# G118_9563_Demo.net
KiCad netlist of a schematic drawn in Altium Designer
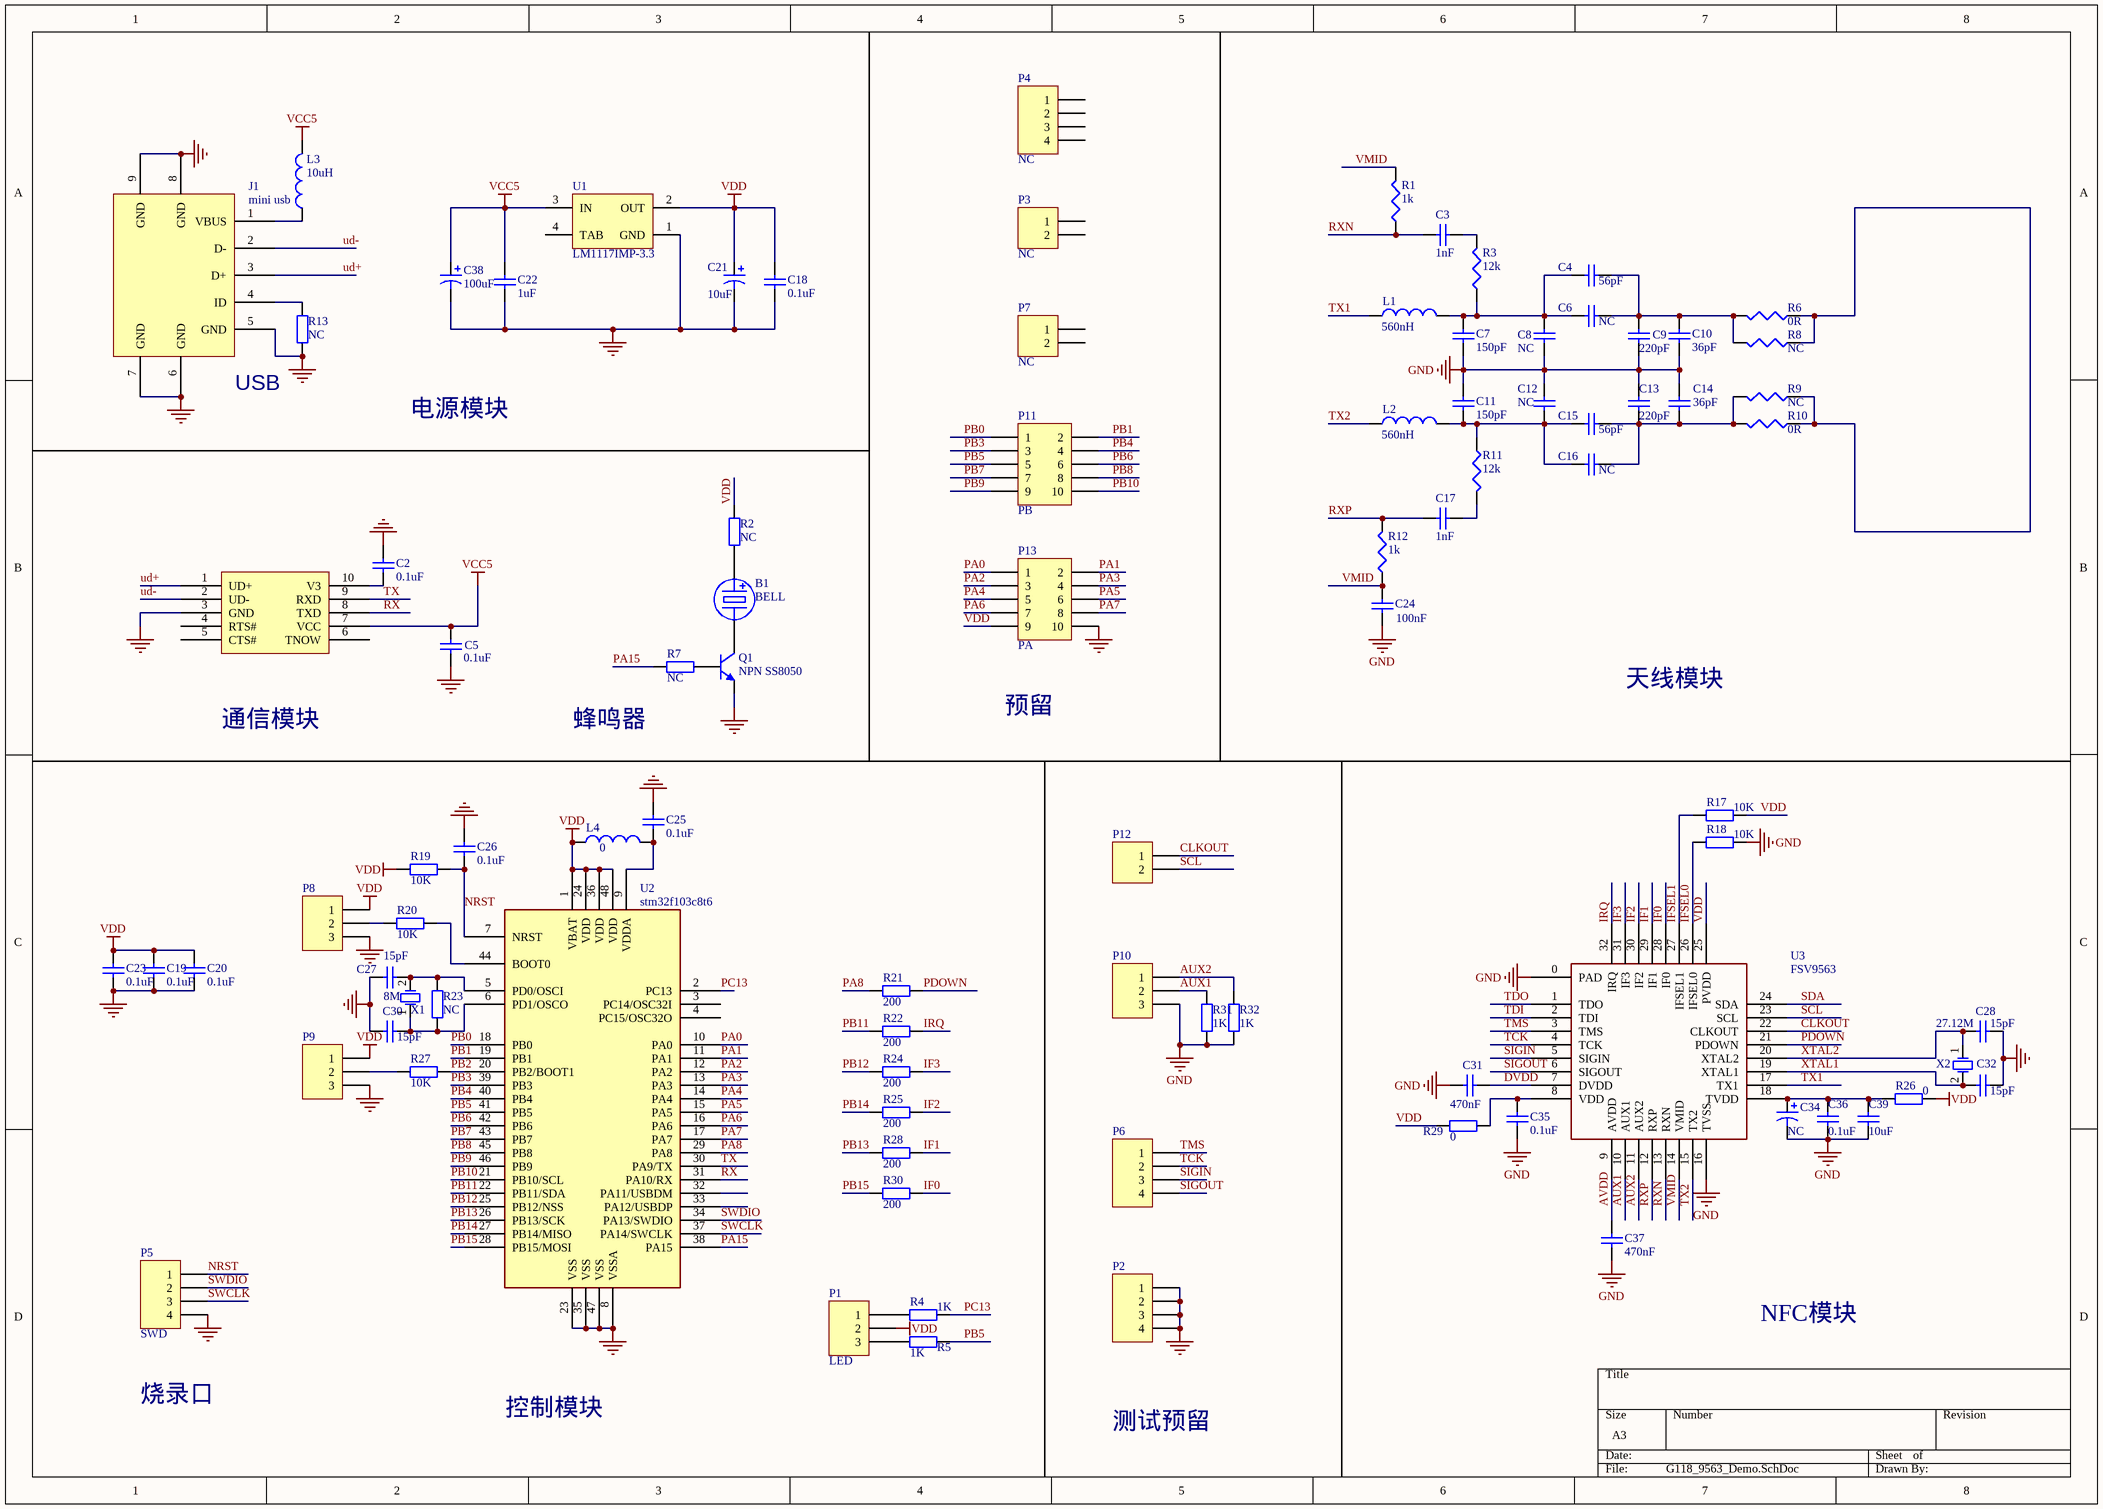
[diagram p0: G118_9563_Demo.SchDoc]

(export (version "E")
  (design (tool "Eeschema 10.0.6"))
  (components
    (comp (ref "B1") (value "BELL") (footprint "BELL_S") (libsource (lib "DevicePlus") (part "BELL")))
    (comp (ref "C2") (value "0.1uF") (footprint "0704C") (libsource (lib "DevicePlus") (part "Capacitor")))
    (comp (ref "C3")
      (value "1nF")
      (footprint "0704C")
      (description "Capacitor (Semiconductor SIM Model)")
      (fields (field (name "Comment") "Cap Semi") (field (name "PUBLISHER") "Altium Limited"))
      (libsource (lib "Miscellaneous Devices") (part "Cap Semi"))
    )
    (comp (ref "C4")
      (value "56pF")
      (footprint "0704C")
      (description "Capacitor (Semiconductor SIM Model)")
      (fields (field (name "Comment") "Cap Semi") (field (name "PUBLISHER") "Altium Limited"))
      (libsource (lib "Miscellaneous Devices") (part "Cap Semi"))
    )
    (comp (ref "C5") (value "0.1uF") (footprint "0704C") (libsource (lib "DevicePlus") (part "Capacitor")))
    (comp (ref "C6")
      (value "NC")
      (footprint "0704C")
      (description "Capacitor (Semiconductor SIM Model)")
      (fields (field (name "Comment") "Cap Semi") (field (name "PUBLISHER") "Altium Limited"))
      (libsource (lib "Miscellaneous Devices") (part "Cap Semi"))
    )
    (comp (ref "C7")
      (value "150pF")
      (footprint "0704C")
      (description "Capacitor (Semiconductor SIM Model)")
      (fields (field (name "Comment") "Cap Semi") (field (name "PUBLISHER") "Altium Limited"))
      (libsource (lib "Miscellaneous Devices") (part "Cap Semi"))
    )
    (comp (ref "C8")
      (value "NC")
      (footprint "0704C")
      (description "Capacitor (Semiconductor SIM Model)")
      (fields (field (name "Comment") "Cap Semi") (field (name "PUBLISHER") "Altium Limited"))
      (libsource (lib "Miscellaneous Devices") (part "Cap Semi"))
    )
    (comp (ref "C9")
      (value "220pF")
      (footprint "0704C")
      (description "Capacitor (Semiconductor SIM Model)")
      (fields (field (name "Comment") "Cap Semi") (field (name "PUBLISHER") "Altium Limited"))
      (libsource (lib "Miscellaneous Devices") (part "Cap Semi"))
    )
    (comp (ref "C10")
      (value "36pF")
      (footprint "0704C")
      (description "Capacitor (Semiconductor SIM Model)")
      (fields (field (name "Comment") "Cap Semi") (field (name "PUBLISHER") "Altium Limited"))
      (libsource (lib "Miscellaneous Devices") (part "Cap Semi"))
    )
    (comp (ref "C11")
      (value "150pF")
      (footprint "0704C")
      (description "Capacitor (Semiconductor SIM Model)")
      (fields (field (name "Comment") "Cap Semi") (field (name "PUBLISHER") "Altium Limited"))
      (libsource (lib "Miscellaneous Devices") (part "Cap Semi"))
    )
    (comp (ref "C12")
      (value "NC")
      (footprint "0704C")
      (description "Capacitor (Semiconductor SIM Model)")
      (fields (field (name "Comment") "Cap Semi") (field (name "PUBLISHER") "Altium Limited"))
      (libsource (lib "Miscellaneous Devices") (part "Cap Semi"))
    )
    (comp (ref "C13")
      (value "220pF")
      (footprint "0704C")
      (description "Capacitor (Semiconductor SIM Model)")
      (fields (field (name "Comment") "Cap Semi") (field (name "PUBLISHER") "Altium Limited"))
      (libsource (lib "Miscellaneous Devices") (part "Cap Semi"))
    )
    (comp (ref "C14")
      (value "36pF")
      (footprint "0704C")
      (description "Capacitor (Semiconductor SIM Model)")
      (fields (field (name "Comment") "Cap Semi") (field (name "PUBLISHER") "Altium Limited"))
      (libsource (lib "Miscellaneous Devices") (part "Cap Semi"))
    )
    (comp (ref "C15")
      (value "56pF")
      (footprint "0704C")
      (description "Capacitor (Semiconductor SIM Model)")
      (fields (field (name "Comment") "Cap Semi") (field (name "PUBLISHER") "Altium Limited"))
      (libsource (lib "Miscellaneous Devices") (part "Cap Semi"))
    )
    (comp (ref "C16")
      (value "NC")
      (footprint "0704C")
      (description "Capacitor (Semiconductor SIM Model)")
      (fields (field (name "Comment") "Cap Semi") (field (name "PUBLISHER") "Altium Limited"))
      (libsource (lib "Miscellaneous Devices") (part "Cap Semi"))
    )
    (comp (ref "C17")
      (value "1nF")
      (footprint "0704C")
      (description "Capacitor (Semiconductor SIM Model)")
      (fields (field (name "Comment") "Cap Semi") (field (name "PUBLISHER") "Altium Limited"))
      (libsource (lib "Miscellaneous Devices") (part "Cap Semi"))
    )
    (comp (ref "C18") (value "0.1uF") (footprint "0704C") (libsource (lib "DevicePlus") (part "Capacitor")))
    (comp (ref "C19") (value "0.1uF") (footprint "0704C") (libsource (lib "DevicePlus") (part "Capacitor")))
    (comp (ref "C20") (value "0.1uF") (footprint "0704C") (libsource (lib "DevicePlus") (part "Capacitor")))
    (comp (ref "C21") (value "10uF") (footprint "RB.1/.2") (libsource (lib "DevicePlus") (part "CapPolar")))
    (comp (ref "C22") (value "1uF") (footprint "0704C") (libsource (lib "DevicePlus") (part "Capacitor")))
    (comp (ref "C23") (value "0.1uF") (footprint "0704C") (libsource (lib "DevicePlus") (part "Capacitor")))
    (comp (ref "C24")
      (value "100nF")
      (footprint "0704C")
      (description "Capacitor (Semiconductor SIM Model)")
      (fields (field (name "PUBLISHER") "Altium Limited"))
      (libsource (lib "Miscellaneous Devices") (part "Cap Semi"))
    )
    (comp (ref "C25") (value "0.1uF") (footprint "0704C") (libsource (lib "DevicePlus") (part "Capacitor")))
    (comp (ref "C26") (value "0.1uF") (footprint "0704C") (libsource (lib "DevicePlus") (part "Capacitor")))
    (comp (ref "C27") (value "15pF") (footprint "0704C") (libsource (lib "DevicePlus") (part "Capacitor")))
    (comp (ref "C28") (value "15pF") (footprint "0704C") (libsource (lib "DevicePlus") (part "Capacitor")))
    (comp (ref "C30") (value "15pF") (footprint "0704C") (libsource (lib "DevicePlus") (part "Capacitor")))
    (comp (ref "C31")
      (value "470nF")
      (footprint "0704C")
      (description "Capacitor (Semiconductor SIM Model)")
      (fields (field (name "Comment") "Cap Semi") (field (name "PUBLISHER") "Altium Limited"))
      (libsource (lib "Miscellaneous Devices") (part "Cap Semi"))
    )
    (comp (ref "C32") (value "15pF") (footprint "0704C") (libsource (lib "DevicePlus") (part "Capacitor")))
    (comp (ref "C34") (value "NC") (footprint "RB.1/.2") (libsource (lib "DevicePlus") (part "CapPolar")))
    (comp (ref "C35") (value "0.1uF") (footprint "0704C") (libsource (lib "DevicePlus") (part "Capacitor")))
    (comp (ref "C36") (value "0.1uF") (footprint "0704C") (libsource (lib "DevicePlus") (part "Capacitor")))
    (comp (ref "C37")
      (value "470nF")
      (footprint "0704C")
      (description "Capacitor (Semiconductor SIM Model)")
      (fields (field (name "Comment") "Cap Semi") (field (name "PUBLISHER") "Altium Limited"))
      (libsource (lib "Miscellaneous Devices") (part "Cap Semi"))
    )
    (comp (ref "C38") (value "100uF") (footprint "RB.1/.2") (libsource (lib "DevicePlus") (part "CapPolar")))
    (comp (ref "C39") (value "10uF") (footprint "0704C") (libsource (lib "DevicePlus") (part "Capacitor")))
    (comp (ref "CH1") (value "CH340E") (footprint "msop-10") (libsource (lib "ch340e") (part "CH340E")))
    (comp (ref "J1")
      (value "mini usb")
      (footprint "usb_mini")
      (libsource (lib "SOCKET_Sch") (part "MINI_USB"))
    )
    (comp (ref "L1")
      (value "560nH")
      (footprint "1210L")
      (description "Inductor")
      (fields (field (name "PUBLISHER") "Altium Limited"))
      (libsource (lib "Miscellaneous Devices") (part "Inductor"))
    )
    (comp (ref "L2")
      (value "560nH")
      (footprint "1210L")
      (description "Inductor")
      (fields (field (name "PUBLISHER") "Altium Limited"))
      (libsource (lib "Miscellaneous Devices") (part "Inductor"))
    )
    (comp (ref "L3") (value "10uH") (footprint "1206") (libsource (lib "DevicePlus") (part "Inductor")))
    (comp (ref "L4") (value "0") (footprint "1206") (libsource (lib "DevicePlus") (part "Inductor")))
    (comp (ref "P1")
      (value "LED")
      (footprint "HDR1X3")
      (description "Header, 3-Pin")
      (fields (field (name "PUBLISHER") "Altium Limited"))
      (libsource (lib "Miscellaneous Connectors") (part "Header 3"))
    )
    (comp (ref "P2")
      (value "~")
      (footprint "HDR1X4")
      (description "Header, 4-Pin")
      (fields (field (name "PUBLISHER") "Altium Limited"))
      (libsource (lib "Miscellaneous Connectors") (part "Header 4"))
    )
    (comp (ref "P3")
      (value "NC")
      (footprint "HDR1X2")
      (description "Header, 2-Pin")
      (fields (field (name "PUBLISHER") "Altium Limited"))
      (libsource (lib "Miscellaneous Connectors") (part "Header 2"))
    )
    (comp (ref "P4")
      (value "NC")
      (footprint "HDR1X4")
      (description "Header, 4-Pin")
      (fields (field (name "PUBLISHER") "Altium Limited"))
      (libsource (lib "Miscellaneous Connectors") (part "Header 4"))
    )
    (comp (ref "P5")
      (value "SWD")
      (footprint "HDR1X4")
      (description "Header, 4-Pin")
      (fields (field (name "PUBLISHER") "Altium Limited"))
      (libsource (lib "Miscellaneous Connectors") (part "Header 4"))
    )
    (comp (ref "P6")
      (value "~")
      (footprint "HDR1X4")
      (description "Header, 4-Pin")
      (fields (field (name "PUBLISHER") "Altium Limited"))
      (libsource (lib "Miscellaneous Connectors") (part "Header 4"))
    )
    (comp (ref "P7")
      (value "NC")
      (footprint "HDR1X2")
      (description "Header, 2-Pin")
      (fields (field (name "PUBLISHER") "Altium Limited"))
      (libsource (lib "Miscellaneous Connectors") (part "Header 2"))
    )
    (comp (ref "P8")
      (value "~")
      (footprint "HDR1X3")
      (description "Header, 3-Pin")
      (fields (field (name "PUBLISHER") "Altium Limited"))
      (libsource (lib "Miscellaneous Connectors") (part "Header 3"))
    )
    (comp (ref "P9")
      (value "~")
      (footprint "HDR1X3")
      (description "Header, 3-Pin")
      (fields (field (name "PUBLISHER") "Altium Limited"))
      (libsource (lib "Miscellaneous Connectors") (part "Header 3"))
    )
    (comp (ref "P10")
      (value "~")
      (footprint "HDR1X3")
      (description "Header, 3-Pin")
      (fields (field (name "PUBLISHER") "Altium Limited"))
      (libsource (lib "Miscellaneous Connectors") (part "Header 3"))
    )
    (comp (ref "P11")
      (value "PB")
      (footprint "HDR2X5")
      (description "Header, 5-Pin, Dual row")
      (fields (field (name "PUBLISHER") "Altium Limited"))
      (libsource (lib "Miscellaneous Connectors") (part "Header 5X2"))
    )
    (comp (ref "P12")
      (value "~")
      (footprint "HDR1X2")
      (description "Header, 2-Pin")
      (fields (field (name "PUBLISHER") "Altium Limited"))
      (libsource (lib "Miscellaneous Connectors") (part "Header 2"))
    )
    (comp (ref "P13")
      (value "PA")
      (footprint "HDR2X5")
      (description "Header, 5-Pin, Dual row")
      (fields (field (name "PUBLISHER") "Altium Limited"))
      (libsource (lib "Miscellaneous Connectors") (part "Header 5X2"))
    )
    (comp (ref "Q1") (value "NPN SS8050") (footprint "SOT-23-2") (libsource (lib "MLIB") (part "NPN SS8050")))
    (comp (ref "R1")
      (value "1k")
      (footprint "0704")
      (description "Resistor")
      (fields (field (name "Comment") "Res3") (field (name "PUBLISHER") "Altium Limited"))
      (libsource (lib "Miscellaneous Devices") (part "Res3"))
    )
    (comp (ref "R2") (value "NC") (footprint "0704") (libsource (lib "") (part "RES_1")))
    (comp (ref "R3")
      (value "12k")
      (footprint "0704")
      (description "Resistor")
      (fields (field (name "Comment") "Res3") (field (name "PUBLISHER") "Altium Limited"))
      (libsource (lib "Miscellaneous Devices") (part "Res3"))
    )
    (comp (ref "R4") (value "1K") (footprint "0704") (libsource (lib "DevicePlus") (part "RES")))
    (comp (ref "R5") (value "1K") (footprint "0704") (libsource (lib "") (part "RES_3")))
    (comp (ref "R6")
      (value "0R")
      (footprint "0704")
      (description "Resistor")
      (fields (field (name "Comment") "Res3") (field (name "PUBLISHER") "Altium Limited"))
      (libsource (lib "Miscellaneous Devices") (part "Res3"))
    )
    (comp (ref "R7") (value "NC") (footprint "0704") (libsource (lib "DevicePlus") (part "RES")))
    (comp (ref "R8")
      (value "NC")
      (footprint "0704")
      (description "Resistor")
      (fields (field (name "Comment") "Res3") (field (name "PUBLISHER") "Altium Limited"))
      (libsource (lib "Miscellaneous Devices") (part "Res3"))
    )
    (comp (ref "R9")
      (value "NC")
      (footprint "0704")
      (description "Resistor")
      (fields (field (name "Comment") "Res3") (field (name "PUBLISHER") "Altium Limited"))
      (libsource (lib "Miscellaneous Devices") (part "Res3"))
    )
    (comp (ref "R10")
      (value "0R")
      (footprint "0704")
      (description "Resistor")
      (fields (field (name "Comment") "Res3") (field (name "PUBLISHER") "Altium Limited"))
      (libsource (lib "Miscellaneous Devices") (part "Res3"))
    )
    (comp (ref "R11")
      (value "12k")
      (footprint "0704")
      (description "Resistor")
      (fields (field (name "Comment") "Res3") (field (name "PUBLISHER") "Altium Limited"))
      (libsource (lib "Miscellaneous Devices") (part "Res3"))
    )
    (comp (ref "R12")
      (value "1k")
      (footprint "0704")
      (description "Resistor")
      (fields (field (name "Comment") "Res3") (field (name "PUBLISHER") "Altium Limited"))
      (libsource (lib "Miscellaneous Devices") (part "Res3"))
    )
    (comp (ref "R13") (value "NC") (footprint "0704") (libsource (lib "") (part "RES_1")))
    (comp (ref "R17") (value "10K") (footprint "0704") (libsource (lib "DevicePlus") (part "RES")))
    (comp (ref "R18") (value "10K") (footprint "0704") (libsource (lib "DevicePlus") (part "RES")))
    (comp (ref "R19") (value "10K") (footprint "0704") (libsource (lib "DevicePlus") (part "RES")))
    (comp (ref "R20") (value "10K") (footprint "0704") (libsource (lib "DevicePlus") (part "RES")))
    (comp (ref "R21") (value "200") (footprint "0704") (libsource (lib "DevicePlus") (part "RES")))
    (comp (ref "R22") (value "200") (footprint "0704") (libsource (lib "DevicePlus") (part "RES")))
    (comp (ref "R23") (value "NC") (footprint "0704") (libsource (lib "") (part "RES_2")))
    (comp (ref "R24") (value "200") (footprint "0704") (libsource (lib "DevicePlus") (part "RES")))
    (comp (ref "R25") (value "200") (footprint "0704") (libsource (lib "DevicePlus") (part "RES")))
    (comp (ref "R26") (value "0") (footprint "0704") (libsource (lib "DevicePlus") (part "RES")))
    (comp (ref "R27") (value "10K") (footprint "0704") (libsource (lib "DevicePlus") (part "RES")))
    (comp (ref "R28") (value "200") (footprint "0704") (libsource (lib "DevicePlus") (part "RES")))
    (comp (ref "R29") (value "0") (footprint "0704") (libsource (lib "DevicePlus") (part "RES")))
    (comp (ref "R30") (value "200") (footprint "0704") (libsource (lib "DevicePlus") (part "RES")))
    (comp (ref "R31") (value "1K") (footprint "0704") (libsource (lib "") (part "RES_2")))
    (comp (ref "R32") (value "1K") (footprint "0704") (libsource (lib "") (part "RES_2")))
    (comp (ref "U1")
      (value "LM1117IMP-3.3")
      (footprint "MP04A_N")
      (description "800mA Low-Dropout Linear Regulator")
      (fields
        (field (name "MANUFACTURER") "National Semiconductor")
        (field (name "DIGIKEYPARTNUMBER") "LM1117IMP-3.3CT-ND")
        (field (name "PUBLISHER") "Altium Limited")
      )
      (libsource (lib "NSC LDO") (part "LM1117IMP-3.3"))
    )
    (comp (ref "U2")
      (value "stm32f103c8t6")
      (footprint "LQFP48L")
      (libsource (lib "IC_Sch") (part "stm32f103c8t6"))
    )
    (comp (ref "U3")
      (value "FSV9563")
      (footprint "QFN-32")
      (description "NFC DRIVER")
      (libsource (lib "IC_Sch") (part "CLRC663"))
    )
    (comp (ref "X1") (value "8M") (footprint "CRYSTAL") (libsource (lib "DevicePlus") (part "Crystal")))
    (comp (ref "X2") (value "27.12M") (footprint "CRYSTAL") (libsource (lib "DevicePlus") (part "Crystal")))
  )
  (nets
    (net (code "1") (name "/AUX1") (class "Default")
      (node (ref "P10") (pin "2") (pinfunction "2_2") (pintype "passive"))
      (node (ref "R31") (pin "2") (pinfunction "2_2") (pintype "passive"))
      (node (ref "U3") (pin "10") (pinfunction "AUX1_10") (pintype "passive"))
    )
    (net (code "2") (name "/AUX2") (class "Default")
      (node (ref "P10") (pin "1") (pinfunction "1_1") (pintype "passive"))
      (node (ref "R32") (pin "2") (pinfunction "2_2") (pintype "passive"))
      (node (ref "U3") (pin "11") (pinfunction "AUX2_11") (pintype "passive"))
    )
    (net (code "3") (name "/AVDD") (class "Default")
      (node (ref "C37") (pin "2") (pinfunction "2_2") (pintype "passive"))
      (node (ref "U3") (pin "9") (pinfunction "AVDD_9") (pintype "passive"))
    )
    (net (code "4") (name "/CLKOUT") (class "Default")
      (node (ref "P12") (pin "1") (pinfunction "1_1") (pintype "passive"))
      (node (ref "U3") (pin "22") (pinfunction "CLKOUT_22") (pintype "passive"))
    )
    (net (code "5") (name "/DVDD") (class "Default")
      (node (ref "C31") (pin "2") (pinfunction "2_2") (pintype "passive"))
      (node (ref "U3") (pin "7") (pinfunction "DVDD_7") (pintype "passive"))
    )
    (net (code "6") (name "/IF0") (class "Default")
      (node (ref "R30") (pin "2") (pinfunction "2_2") (pintype "passive"))
      (node (ref "U3") (pin "28") (pinfunction "IF0_28") (pintype "passive"))
    )
    (net (code "7") (name "/IF1") (class "Default")
      (node (ref "R28") (pin "2") (pinfunction "2_2") (pintype "passive"))
      (node (ref "U3") (pin "29") (pinfunction "IF1_29") (pintype "passive"))
    )
    (net (code "8") (name "/IF2") (class "Default")
      (node (ref "R25") (pin "2") (pinfunction "2_2") (pintype "passive"))
      (node (ref "U3") (pin "30") (pinfunction "IF2_30") (pintype "passive"))
    )
    (net (code "9") (name "/IF3") (class "Default")
      (node (ref "R24") (pin "2") (pinfunction "2_2") (pintype "passive"))
      (node (ref "U3") (pin "31") (pinfunction "IF3_31") (pintype "passive"))
    )
    (net (code "10") (name "/IFSEL0") (class "Default")
      (node (ref "R18") (pin "1") (pinfunction "1_1") (pintype "passive"))
      (node (ref "U3") (pin "26") (pinfunction "IFSEL0_26") (pintype "passive"))
    )
    (net (code "11") (name "/IFSEL1") (class "Default")
      (node (ref "R17") (pin "1") (pinfunction "1_1") (pintype "passive"))
      (node (ref "U3") (pin "27") (pinfunction "IFSEL1_27") (pintype "passive"))
    )
    (net (code "12") (name "/IRQ") (class "Default")
      (node (ref "R22") (pin "2") (pinfunction "2_2") (pintype "passive"))
      (node (ref "U3") (pin "32") (pinfunction "IRQ_32") (pintype "passive"))
    )
    (net (code "13") (name "/NRST") (class "Default")
      (node (ref "C26") (pin "2") (pinfunction "2_2") (pintype "passive"))
      (node (ref "P5") (pin "1") (pinfunction "1_1") (pintype "passive"))
      (node (ref "R19") (pin "2") (pinfunction "2_2") (pintype "passive"))
      (node (ref "U2") (pin "7") (pinfunction "NRST_7") (pintype "passive"))
    )
    (net (code "14") (name "/PA0") (class "Default")
      (node (ref "P13") (pin "1") (pinfunction "1_1") (pintype "passive"))
      (node (ref "U2") (pin "10") (pinfunction "PA0_10") (pintype "passive"))
    )
    (net (code "15") (name "/PA1") (class "Default")
      (node (ref "P13") (pin "2") (pinfunction "2_2") (pintype "passive"))
      (node (ref "U2") (pin "11") (pinfunction "PA1_11") (pintype "passive"))
    )
    (net (code "16") (name "/PA2") (class "Default")
      (node (ref "P13") (pin "3") (pinfunction "3_3") (pintype "passive"))
      (node (ref "U2") (pin "12") (pinfunction "PA2_12") (pintype "passive"))
    )
    (net (code "17") (name "/PA3") (class "Default")
      (node (ref "P13") (pin "4") (pinfunction "4_4") (pintype "passive"))
      (node (ref "U2") (pin "13") (pinfunction "PA3_13") (pintype "passive"))
    )
    (net (code "18") (name "/PA4") (class "Default")
      (node (ref "P13") (pin "5") (pinfunction "5_5") (pintype "passive"))
      (node (ref "U2") (pin "14") (pinfunction "PA4_14") (pintype "passive"))
    )
    (net (code "19") (name "/PA5") (class "Default")
      (node (ref "P13") (pin "6") (pinfunction "6_6") (pintype "passive"))
      (node (ref "U2") (pin "15") (pinfunction "PA5_15") (pintype "passive"))
    )
    (net (code "20") (name "/PA6") (class "Default")
      (node (ref "P13") (pin "7") (pinfunction "7_7") (pintype "passive"))
      (node (ref "U2") (pin "16") (pinfunction "PA6_16") (pintype "passive"))
    )
    (net (code "21") (name "/PA7") (class "Default")
      (node (ref "P13") (pin "8") (pinfunction "8_8") (pintype "passive"))
      (node (ref "U2") (pin "17") (pinfunction "PA7_17") (pintype "passive"))
    )
    (net (code "22") (name "/PA8") (class "Default")
      (node (ref "R21") (pin "1") (pinfunction "1_1") (pintype "passive"))
      (node (ref "U2") (pin "29") (pinfunction "PA8_29") (pintype "passive"))
    )
    (net (code "23") (name "/PA15") (class "Default")
      (node (ref "R7") (pin "1") (pinfunction "1_1") (pintype "passive"))
      (node (ref "U2") (pin "38") (pinfunction "PA15_38") (pintype "passive"))
    )
    (net (code "24") (name "/PB0") (class "Default")
      (node (ref "P11") (pin "1") (pinfunction "1_1") (pintype "passive"))
      (node (ref "U2") (pin "18") (pinfunction "PB0_18") (pintype "passive"))
    )
    (net (code "25") (name "/PB1") (class "Default")
      (node (ref "P11") (pin "2") (pinfunction "2_2") (pintype "passive"))
      (node (ref "U2") (pin "19") (pinfunction "PB1_19") (pintype "passive"))
    )
    (net (code "26") (name "/PB2") (class "Default")
      (node (ref "R27") (pin "2") (pinfunction "2_2") (pintype "passive"))
      (node (ref "U2") (pin "20") (pinfunction "PB2/BOOT1_20") (pintype "passive"))
    )
    (net (code "27") (name "/PB3") (class "Default")
      (node (ref "P11") (pin "3") (pinfunction "3_3") (pintype "passive"))
      (node (ref "U2") (pin "39") (pinfunction "PB3_39") (pintype "passive"))
    )
    (net (code "28") (name "/PB4") (class "Default")
      (node (ref "P11") (pin "4") (pinfunction "4_4") (pintype "passive"))
      (node (ref "U2") (pin "40") (pinfunction "PB4_40") (pintype "passive"))
    )
    (net (code "29") (name "/PB5") (class "Default")
      (node (ref "P11") (pin "5") (pinfunction "5_5") (pintype "passive"))
      (node (ref "R5") (pin "1") (pinfunction "1_1") (pintype "passive"))
      (node (ref "U2") (pin "41") (pinfunction "PB5_41") (pintype "passive"))
    )
    (net (code "30") (name "/PB6") (class "Default")
      (node (ref "P11") (pin "6") (pinfunction "6_6") (pintype "passive"))
      (node (ref "U2") (pin "42") (pinfunction "PB6_42") (pintype "passive"))
    )
    (net (code "31") (name "/PB7") (class "Default")
      (node (ref "P11") (pin "7") (pinfunction "7_7") (pintype "passive"))
      (node (ref "U2") (pin "43") (pinfunction "PB7_43") (pintype "passive"))
    )
    (net (code "32") (name "/PB8") (class "Default")
      (node (ref "P11") (pin "8") (pinfunction "8_8") (pintype "passive"))
      (node (ref "U2") (pin "45") (pinfunction "PB8_45") (pintype "passive"))
    )
    (net (code "33") (name "/PB9") (class "Default")
      (node (ref "P11") (pin "9") (pinfunction "9_9") (pintype "passive"))
      (node (ref "U2") (pin "46") (pinfunction "PB9_46") (pintype "passive"))
    )
    (net (code "34") (name "/PB10") (class "Default")
      (node (ref "P11") (pin "10") (pinfunction "10_10") (pintype "passive"))
      (node (ref "U2") (pin "21") (pinfunction "PB10/SCL_21") (pintype "passive"))
    )
    (net (code "35") (name "/PB11") (class "Default")
      (node (ref "R22") (pin "1") (pinfunction "1_1") (pintype "passive"))
      (node (ref "U2") (pin "22") (pinfunction "PB11/SDA_22") (pintype "passive"))
    )
    (net (code "36") (name "/PB12") (class "Default")
      (node (ref "R24") (pin "1") (pinfunction "1_1") (pintype "passive"))
      (node (ref "U2") (pin "25") (pinfunction "PB12/NSS_25") (pintype "passive"))
    )
    (net (code "37") (name "/PB13") (class "Default")
      (node (ref "R28") (pin "1") (pinfunction "1_1") (pintype "passive"))
      (node (ref "U2") (pin "26") (pinfunction "PB13/SCK_26") (pintype "passive"))
    )
    (net (code "38") (name "/PB14") (class "Default")
      (node (ref "R25") (pin "1") (pinfunction "1_1") (pintype "passive"))
      (node (ref "U2") (pin "27") (pinfunction "PB14/MISO_27") (pintype "passive"))
    )
    (net (code "39") (name "/PB15") (class "Default")
      (node (ref "R30") (pin "1") (pinfunction "1_1") (pintype "passive"))
      (node (ref "U2") (pin "28") (pinfunction "PB15/MOSI_28") (pintype "passive"))
    )
    (net (code "40") (name "/PC13") (class "Default")
      (node (ref "R4") (pin "2") (pinfunction "2_2") (pintype "passive"))
      (node (ref "U2") (pin "2") (pinfunction "PC13_2") (pintype "passive"))
    )
    (net (code "41") (name "/PDOWN") (class "Default")
      (node (ref "R21") (pin "2") (pinfunction "2_2") (pintype "passive"))
      (node (ref "U3") (pin "21") (pinfunction "PDOWN_21") (pintype "passive"))
    )
    (net (code "42") (name "/RX") (class "Default")
      (node (ref "CH1") (pin "8") (pinfunction "TXD_8") (pintype "passive"))
      (node (ref "U2") (pin "31") (pinfunction "PA10/RX_31") (pintype "passive"))
    )
    (net (code "43") (name "/RXN") (class "Default")
      (node (ref "C3") (pin "2") (pinfunction "2_2") (pintype "passive"))
      (node (ref "R1") (pin "1") (pinfunction "1_1") (pintype "passive"))
      (node (ref "U3") (pin "13") (pinfunction "RXN_13") (pintype "passive"))
    )
    (net (code "44") (name "/RXP") (class "Default")
      (node (ref "C17") (pin "2") (pinfunction "2_2") (pintype "passive"))
      (node (ref "R12") (pin "1") (pinfunction "1_1") (pintype "passive"))
      (node (ref "U3") (pin "12") (pinfunction "RXP_12") (pintype "passive"))
    )
    (net (code "45") (name "/SCL") (class "Default")
      (node (ref "P12") (pin "2") (pinfunction "2_2") (pintype "passive"))
      (node (ref "U3") (pin "23") (pinfunction "SCL_23") (pintype "passive"))
    )
    (net (code "46") (name "/SDA") (class "Default")
      (node (ref "U3") (pin "24") (pinfunction "SDA_24") (pintype "passive"))
    )
    (net (code "47") (name "/SIGIN") (class "Default")
      (node (ref "P6") (pin "3") (pinfunction "3_3") (pintype "passive"))
      (node (ref "U3") (pin "5") (pinfunction "SIGIN_5") (pintype "passive"))
    )
    (net (code "48") (name "/SIGOUT") (class "Default")
      (node (ref "P6") (pin "4") (pinfunction "4_4") (pintype "passive"))
      (node (ref "U3") (pin "6") (pinfunction "SIGOUT_6") (pintype "passive"))
    )
    (net (code "49") (name "/SWCLK") (class "Default")
      (node (ref "P5") (pin "3") (pinfunction "3_3") (pintype "passive"))
      (node (ref "U2") (pin "37") (pinfunction "PA14/SWCLK_37") (pintype "passive"))
    )
    (net (code "50") (name "/SWDIO") (class "Default")
      (node (ref "P5") (pin "2") (pinfunction "2_2") (pintype "passive"))
      (node (ref "U2") (pin "34") (pinfunction "PA13/SWDIO_34") (pintype "passive"))
    )
    (net (code "51") (name "/TCK") (class "Default")
      (node (ref "P6") (pin "2") (pinfunction "2_2") (pintype "passive"))
      (node (ref "U3") (pin "4") (pinfunction "TCK_4") (pintype "passive"))
    )
    (net (code "52") (name "/TDI") (class "Default")
      (node (ref "U3") (pin "2") (pinfunction "TDI_2") (pintype "passive"))
    )
    (net (code "53") (name "/TDO") (class "Default")
      (node (ref "U3") (pin "1") (pinfunction "TDO_1") (pintype "passive"))
    )
    (net (code "54") (name "/TMS") (class "Default")
      (node (ref "P6") (pin "1") (pinfunction "1_1") (pintype "passive"))
      (node (ref "U3") (pin "3") (pinfunction "TMS_3") (pintype "passive"))
    )
    (net (code "55") (name "/TX") (class "Default")
      (node (ref "CH1") (pin "9") (pinfunction "RXD_9") (pintype "passive"))
      (node (ref "U2") (pin "30") (pinfunction "PA9/TX_30") (pintype "passive"))
    )
    (net (code "56") (name "/TX1") (class "Default")
      (node (ref "L1") (pin "1") (pinfunction "1_1") (pintype "passive"))
      (node (ref "U3") (pin "17") (pinfunction "TX1_17") (pintype "passive"))
    )
    (net (code "57") (name "/TX2") (class "Default")
      (node (ref "L2") (pin "1") (pinfunction "1_1") (pintype "passive"))
      (node (ref "U3") (pin "15") (pinfunction "TX2_15") (pintype "passive"))
    )
    (net (code "58") (name "/VMID") (class "Default")
      (node (ref "C24") (pin "1") (pinfunction "1_1") (pintype "passive"))
      (node (ref "R1") (pin "2") (pinfunction "2_2") (pintype "passive"))
      (node (ref "R12") (pin "2") (pinfunction "2_2") (pintype "passive"))
      (node (ref "U3") (pin "14") (pinfunction "VMID_14") (pintype "passive"))
    )
    (net (code "59") (name "/XTAL1") (class "Default")
      (node (ref "C32") (pin "2") (pinfunction "2_2") (pintype "passive"))
      (node (ref "U3") (pin "19") (pinfunction "XTAL1_19") (pintype "passive"))
      (node (ref "X2") (pin "2") (pinfunction "OSC2_2") (pintype "passive"))
    )
    (net (code "60") (name "/XTAL2") (class "Default")
      (node (ref "C28") (pin "2") (pinfunction "2_2") (pintype "passive"))
      (node (ref "U3") (pin "20") (pinfunction "XTAL2_20") (pintype "passive"))
      (node (ref "X2") (pin "1") (pinfunction "OSC1_1") (pintype "passive"))
    )
    (net (code "61") (name "/ud+") (class "Default")
      (node (ref "CH1") (pin "1") (pinfunction "UD+_1") (pintype "power_in"))
      (node (ref "J1") (pin "3") (pinfunction "D+_3") (pintype "passive"))
    )
    (net (code "62") (name "/ud-") (class "Default")
      (node (ref "CH1") (pin "2") (pinfunction "UD-_2") (pintype "passive"))
      (node (ref "J1") (pin "2") (pinfunction "D-_2") (pintype "passive"))
    )
    (net (code "63") (name "GND") (class "Default")
      (node (ref "C10") (pin "2") (pinfunction "2_2") (pintype "passive"))
      (node (ref "C11") (pin "1") (pinfunction "1_1") (pintype "passive"))
      (node (ref "C12") (pin "1") (pinfunction "1_1") (pintype "passive"))
      (node (ref "C13") (pin "1") (pinfunction "1_1") (pintype "passive"))
      (node (ref "C14") (pin "1") (pinfunction "1_1") (pintype "passive"))
      (node (ref "C18") (pin "2") (pinfunction "2_2") (pintype "passive"))
      (node (ref "C19") (pin "2") (pinfunction "2_2") (pintype "passive"))
      (node (ref "C2") (pin "2") (pinfunction "2_2") (pintype "passive"))
      (node (ref "C20") (pin "2") (pinfunction "2_2") (pintype "passive"))
      (node (ref "C21") (pin "2") (pinfunction "2_2") (pintype "passive"))
      (node (ref "C22") (pin "2") (pinfunction "2_2") (pintype "passive"))
      (node (ref "C23") (pin "2") (pinfunction "2_2") (pintype "passive"))
      (node (ref "C24") (pin "2") (pinfunction "2_2") (pintype "passive"))
      (node (ref "C25") (pin "1") (pinfunction "1_1") (pintype "passive"))
      (node (ref "C26") (pin "1") (pinfunction "1_1") (pintype "passive"))
      (node (ref "C27") (pin "1") (pinfunction "1_1") (pintype "passive"))
      (node (ref "C28") (pin "1") (pinfunction "1_1") (pintype "passive"))
      (node (ref "C30") (pin "1") (pinfunction "1_1") (pintype "passive"))
      (node (ref "C31") (pin "1") (pinfunction "1_1") (pintype "passive"))
      (node (ref "C32") (pin "1") (pinfunction "1_1") (pintype "passive"))
      (node (ref "C34") (pin "2") (pinfunction "2_2") (pintype "passive"))
      (node (ref "C35") (pin "2") (pinfunction "2_2") (pintype "passive"))
      (node (ref "C36") (pin "2") (pinfunction "2_2") (pintype "passive"))
      (node (ref "C37") (pin "1") (pinfunction "1_1") (pintype "passive"))
      (node (ref "C38") (pin "2") (pinfunction "2_2") (pintype "passive"))
      (node (ref "C39") (pin "2") (pinfunction "2_2") (pintype "passive"))
      (node (ref "C5") (pin "2") (pinfunction "2_2") (pintype "passive"))
      (node (ref "C7") (pin "2") (pinfunction "2_2") (pintype "passive"))
      (node (ref "C8") (pin "2") (pinfunction "2_2") (pintype "passive"))
      (node (ref "C9") (pin "2") (pinfunction "2_2") (pintype "passive"))
      (node (ref "CH1") (pin "3") (pinfunction "GND_3") (pintype "passive"))
      (node (ref "J1") (pin "5") (pinfunction "GND_5") (pintype "passive"))
      (node (ref "J1") (pin "6") (pinfunction "GND_6") (pintype "passive"))
      (node (ref "J1") (pin "7") (pinfunction "GND_7") (pintype "passive"))
      (node (ref "J1") (pin "8") (pinfunction "GND_8") (pintype "passive"))
      (node (ref "J1") (pin "9") (pinfunction "GND_9") (pintype "passive"))
      (node (ref "P10") (pin "3") (pinfunction "3_3") (pintype "passive"))
      (node (ref "P13") (pin "10") (pinfunction "10_10") (pintype "passive"))
      (node (ref "P2") (pin "1") (pinfunction "1_1") (pintype "passive"))
      (node (ref "P2") (pin "2") (pinfunction "2_2") (pintype "passive"))
      (node (ref "P2") (pin "3") (pinfunction "3_3") (pintype "passive"))
      (node (ref "P2") (pin "4") (pinfunction "4_4") (pintype "passive"))
      (node (ref "P5") (pin "4") (pinfunction "4_4") (pintype "passive"))
      (node (ref "P8") (pin "3") (pinfunction "3_3") (pintype "passive"))
      (node (ref "P9") (pin "3") (pinfunction "3_3") (pintype "passive"))
      (node (ref "Q1") (pin "3") (pinfunction "3_3") (pintype "passive"))
      (node (ref "R13") (pin "2") (pinfunction "2_2") (pintype "passive"))
      (node (ref "R18") (pin "2") (pinfunction "2_2") (pintype "passive"))
      (node (ref "R31") (pin "1") (pinfunction "1_1") (pintype "passive"))
      (node (ref "R32") (pin "1") (pinfunction "1_1") (pintype "passive"))
      (node (ref "U1") (pin "1") (pinfunction "GND_1") (pintype "power_in"))
      (node (ref "U2") (pin "23") (pinfunction "VSS_23") (pintype "passive"))
      (node (ref "U2") (pin "35") (pinfunction "VSS_35") (pintype "passive"))
      (node (ref "U2") (pin "47") (pinfunction "VSS_47") (pintype "passive"))
      (node (ref "U2") (pin "8") (pinfunction "VSSA_8") (pintype "passive"))
      (node (ref "U3") (pin "0") (pinfunction "PAD_0") (pintype "passive"))
      (node (ref "U3") (pin "16") (pinfunction "TVSS_16") (pintype "passive"))
    )
    (net (code "64") (name "Net-(B1-+)") (class "Default")
      (node (ref "B1") (pin "1") (pinfunction "+_1") (pintype "passive"))
      (node (ref "R2") (pin "2") (pinfunction "2_2") (pintype "passive"))
    )
    (net (code "65") (name "Net-(B1--)") (class "Default")
      (node (ref "B1") (pin "2") (pinfunction "-_2") (pintype "passive"))
      (node (ref "Q1") (pin "1") (pinfunction "1_1") (pintype "passive"))
    )
    (net (code "66") (name "Net-(C3-Pad1)") (class "Default")
      (node (ref "C3") (pin "1") (pinfunction "1_1") (pintype "passive"))
      (node (ref "R3") (pin "2") (pinfunction "2_2") (pintype "passive"))
    )
    (net (code "67") (name "Net-(C4-Pad1)") (class "Default")
      (node (ref "C4") (pin "1") (pinfunction "1_1") (pintype "passive"))
      (node (ref "C6") (pin "2") (pinfunction "2_2") (pintype "passive"))
      (node (ref "C7") (pin "1") (pinfunction "1_1") (pintype "passive"))
      (node (ref "C8") (pin "1") (pinfunction "1_1") (pintype "passive"))
      (node (ref "L1") (pin "2") (pinfunction "2_2") (pintype "passive"))
      (node (ref "R3") (pin "1") (pinfunction "1_1") (pintype "passive"))
    )
    (net (code "68") (name "Net-(C10-Pad1)") (class "Default")
      (node (ref "C10") (pin "1") (pinfunction "1_1") (pintype "passive"))
      (node (ref "C4") (pin "2") (pinfunction "2_2") (pintype "passive"))
      (node (ref "C6") (pin "1") (pinfunction "1_1") (pintype "passive"))
      (node (ref "C9") (pin "1") (pinfunction "1_1") (pintype "passive"))
      (node (ref "R6") (pin "2") (pinfunction "2_2") (pintype "passive"))
      (node (ref "R8") (pin "2") (pinfunction "2_2") (pintype "passive"))
    )
    (net (code "69") (name "Net-(C11-Pad2)") (class "Default")
      (node (ref "C11") (pin "2") (pinfunction "2_2") (pintype "passive"))
      (node (ref "C12") (pin "2") (pinfunction "2_2") (pintype "passive"))
      (node (ref "C15") (pin "2") (pinfunction "2_2") (pintype "passive"))
      (node (ref "C16") (pin "1") (pinfunction "1_1") (pintype "passive"))
      (node (ref "L2") (pin "2") (pinfunction "2_2") (pintype "passive"))
      (node (ref "R11") (pin "2") (pinfunction "2_2") (pintype "passive"))
    )
    (net (code "70") (name "Net-(C13-Pad2)") (class "Default")
      (node (ref "C13") (pin "2") (pinfunction "2_2") (pintype "passive"))
      (node (ref "C14") (pin "2") (pinfunction "2_2") (pintype "passive"))
      (node (ref "C15") (pin "1") (pinfunction "1_1") (pintype "passive"))
      (node (ref "C16") (pin "2") (pinfunction "2_2") (pintype "passive"))
      (node (ref "R10") (pin "2") (pinfunction "2_2") (pintype "passive"))
      (node (ref "R9") (pin "2") (pinfunction "2_2") (pintype "passive"))
    )
    (net (code "71") (name "Net-(C17-Pad1)") (class "Default")
      (node (ref "C17") (pin "1") (pinfunction "1_1") (pintype "passive"))
      (node (ref "R11") (pin "1") (pinfunction "1_1") (pintype "passive"))
    )
    (net (code "72") (name "Net-(CH1-V3)") (class "Default")
      (node (ref "C2") (pin "1") (pinfunction "1_1") (pintype "passive"))
      (node (ref "CH1") (pin "10") (pinfunction "V3_10") (pintype "power_in"))
    )
    (net (code "73") (name "Net-(J1-ID)") (class "Default")
      (node (ref "J1") (pin "4") (pinfunction "ID_4") (pintype "passive"))
      (node (ref "R13") (pin "1") (pinfunction "1_1") (pintype "passive"))
    )
    (net (code "74") (name "Net-(J1-VBUS)") (class "Default")
      (node (ref "J1") (pin "1") (pinfunction "VBUS_1") (pintype "passive"))
      (node (ref "L3") (pin "1") (pinfunction "1_1") (pintype "passive"))
    )
    (net (code "75") (name "Net-(P1-Pad1)") (class "Default")
      (node (ref "P1") (pin "1") (pinfunction "1_1") (pintype "passive"))
      (node (ref "R4") (pin "1") (pinfunction "1_1") (pintype "passive"))
    )
    (net (code "76") (name "Net-(P1-Pad3)") (class "Default")
      (node (ref "P1") (pin "3") (pinfunction "3_3") (pintype "passive"))
      (node (ref "R5") (pin "2") (pinfunction "2_2") (pintype "passive"))
    )
    (net (code "77") (name "Net-(P8-Pad2)") (class "Default")
      (node (ref "P8") (pin "2") (pinfunction "2_2") (pintype "passive"))
      (node (ref "R20") (pin "1") (pinfunction "1_1") (pintype "passive"))
    )
    (net (code "78") (name "Net-(P9-Pad2)") (class "Default")
      (node (ref "P9") (pin "2") (pinfunction "2_2") (pintype "passive"))
      (node (ref "R27") (pin "1") (pinfunction "1_1") (pintype "passive"))
    )
    (net (code "79") (name "Net-(Q1-Pad2)") (class "Default")
      (node (ref "Q1") (pin "2") (pinfunction "2_2") (pintype "passive"))
      (node (ref "R7") (pin "2") (pinfunction "2_2") (pintype "passive"))
    )
    (net (code "80") (name "Net-(R10-Pad1)") (class "Default")
      (node (ref "R10") (pin "1") (pinfunction "1_1") (pintype "passive"))
      (node (ref "R6") (pin "1") (pinfunction "1_1") (pintype "passive"))
      (node (ref "R8") (pin "1") (pinfunction "1_1") (pintype "passive"))
      (node (ref "R9") (pin "1") (pinfunction "1_1") (pintype "passive"))
    )
    (net (code "81") (name "Net-(U2-BOOT0)") (class "Default")
      (node (ref "R20") (pin "2") (pinfunction "2_2") (pintype "passive"))
      (node (ref "U2") (pin "44") (pinfunction "BOOT0_44") (pintype "passive"))
    )
    (net (code "82") (name "Net-(U2-PD0{slash}OSCI)") (class "Default")
      (node (ref "C27") (pin "2") (pinfunction "2_2") (pintype "passive"))
      (node (ref "R23") (pin "2") (pinfunction "2_2") (pintype "passive"))
      (node (ref "U2") (pin "5") (pinfunction "PD0/OSCI_5") (pintype "passive"))
      (node (ref "X1") (pin "2") (pinfunction "OSC2_2") (pintype "passive"))
    )
    (net (code "83") (name "Net-(U2-PD1{slash}OSCO)") (class "Default")
      (node (ref "C30") (pin "2") (pinfunction "2_2") (pintype "passive"))
      (node (ref "R23") (pin "1") (pinfunction "1_1") (pintype "passive"))
      (node (ref "U2") (pin "6") (pinfunction "PD1/OSCO_6") (pintype "passive"))
      (node (ref "X1") (pin "1") (pinfunction "OSC1_1") (pintype "passive"))
    )
    (net (code "84") (name "Net-(U2-VDDA)") (class "Default")
      (node (ref "C25") (pin "2") (pinfunction "2_2") (pintype "passive"))
      (node (ref "L4") (pin "2") (pinfunction "2_2") (pintype "passive"))
      (node (ref "U2") (pin "9") (pinfunction "VDDA_9") (pintype "passive"))
    )
    (net (code "85") (name "Net-(U3-TVDD)") (class "Default")
      (node (ref "C34") (pin "1") (pinfunction "1_1") (pintype "passive"))
      (node (ref "C36") (pin "1") (pinfunction "1_1") (pintype "passive"))
      (node (ref "C39") (pin "1") (pinfunction "1_1") (pintype "passive"))
      (node (ref "R26") (pin "1") (pinfunction "1_1") (pintype "passive"))
      (node (ref "U3") (pin "18") (pinfunction "TVDD_18") (pintype "passive"))
    )
    (net (code "86") (name "Net-(U3-VDD)") (class "Default")
      (node (ref "C35") (pin "1") (pinfunction "1_1") (pintype "passive"))
      (node (ref "R29") (pin "2") (pinfunction "2_2") (pintype "passive"))
      (node (ref "U3") (pin "8") (pinfunction "VDD_8") (pintype "passive"))
    )
    (net (code "87") (name "VCC5") (class "Default")
      (node (ref "C22") (pin "1") (pinfunction "1_1") (pintype "passive"))
      (node (ref "C38") (pin "1") (pinfunction "1_1") (pintype "passive"))
      (node (ref "C5") (pin "1") (pinfunction "1_1") (pintype "passive"))
      (node (ref "CH1") (pin "7") (pinfunction "VCC_7") (pintype "passive"))
      (node (ref "L3") (pin "2") (pinfunction "2_2") (pintype "passive"))
      (node (ref "U1") (pin "3") (pinfunction "IN_3") (pintype "power_in"))
    )
    (net (code "88") (name "VDD") (class "Default")
      (node (ref "C18") (pin "1") (pinfunction "1_1") (pintype "passive"))
      (node (ref "C19") (pin "1") (pinfunction "1_1") (pintype "passive"))
      (node (ref "C20") (pin "1") (pinfunction "1_1") (pintype "passive"))
      (node (ref "C21") (pin "1") (pinfunction "1_1") (pintype "passive"))
      (node (ref "C23") (pin "1") (pinfunction "1_1") (pintype "passive"))
      (node (ref "L4") (pin "1") (pinfunction "1_1") (pintype "passive"))
      (node (ref "P1") (pin "2") (pinfunction "2_2") (pintype "passive"))
      (node (ref "P13") (pin "9") (pinfunction "9_9") (pintype "passive"))
      (node (ref "P8") (pin "1") (pinfunction "1_1") (pintype "passive"))
      (node (ref "P9") (pin "1") (pinfunction "1_1") (pintype "passive"))
      (node (ref "R17") (pin "2") (pinfunction "2_2") (pintype "passive"))
      (node (ref "R19") (pin "1") (pinfunction "1_1") (pintype "passive"))
      (node (ref "R2") (pin "1") (pinfunction "1_1") (pintype "passive"))
      (node (ref "R26") (pin "2") (pinfunction "2_2") (pintype "passive"))
      (node (ref "R29") (pin "1") (pinfunction "1_1") (pintype "passive"))
      (node (ref "U1") (pin "2") (pinfunction "OUT_2") (pintype "power_in"))
      (node (ref "U2") (pin "1") (pinfunction "VBAT_1") (pintype "passive"))
      (node (ref "U2") (pin "24") (pinfunction "VDD_24") (pintype "passive"))
      (node (ref "U2") (pin "36") (pinfunction "VDD_36") (pintype "passive"))
      (node (ref "U2") (pin "48") (pinfunction "VDD_48") (pintype "passive"))
      (node (ref "U3") (pin "25") (pinfunction "PVDD_25") (pintype "passive"))
    )
    (net (code "89") (name "unconnected-(CH1-CTS#-Pad5)") (class "Default")
      (node (ref "CH1") (pin "5") (pinfunction "CTS#_5") (pintype "passive"))
    )
    (net (code "90") (name "unconnected-(CH1-RTS#-Pad4)") (class "Default")
      (node (ref "CH1") (pin "4") (pinfunction "RTS#_4") (pintype "power_in"))
    )
    (net (code "91") (name "unconnected-(CH1-TNOW-Pad6)") (class "Default")
      (node (ref "CH1") (pin "6") (pinfunction "TNOW_6") (pintype "passive"))
    )
    (net (code "92") (name "unconnected-(P3-Pad1)") (class "Default")
      (node (ref "P3") (pin "1") (pinfunction "1_1") (pintype "passive"))
    )
    (net (code "93") (name "unconnected-(P3-Pad2)") (class "Default")
      (node (ref "P3") (pin "2") (pinfunction "2_2") (pintype "passive"))
    )
    (net (code "94") (name "unconnected-(P4-Pad1)") (class "Default")
      (node (ref "P4") (pin "1") (pinfunction "1_1") (pintype "passive"))
    )
    (net (code "95") (name "unconnected-(P4-Pad2)") (class "Default")
      (node (ref "P4") (pin "2") (pinfunction "2_2") (pintype "passive"))
    )
    (net (code "96") (name "unconnected-(P4-Pad3)") (class "Default")
      (node (ref "P4") (pin "3") (pinfunction "3_3") (pintype "passive"))
    )
    (net (code "97") (name "unconnected-(P4-Pad4)") (class "Default")
      (node (ref "P4") (pin "4") (pinfunction "4_4") (pintype "passive"))
    )
    (net (code "98") (name "unconnected-(P7-Pad1)") (class "Default")
      (node (ref "P7") (pin "1") (pinfunction "1_1") (pintype "passive"))
    )
    (net (code "99") (name "unconnected-(P7-Pad2)") (class "Default")
      (node (ref "P7") (pin "2") (pinfunction "2_2") (pintype "passive"))
    )
    (net (code "100") (name "unconnected-(U1-TAB-Pad4)") (class "Default")
      (node (ref "U1") (pin "4") (pinfunction "TAB_4") (pintype "power_in"))
    )
    (net (code "101") (name "unconnected-(U2-PA11{slash}USBDM-Pad32)") (class "Default")
      (node (ref "U2") (pin "32") (pinfunction "PA11/USBDM_32") (pintype "passive"))
    )
    (net (code "102") (name "unconnected-(U2-PA12{slash}USBDP-Pad33)") (class "Default")
      (node (ref "U2") (pin "33") (pinfunction "PA12/USBDP_33") (pintype "passive"))
    )
    (net (code "103") (name "unconnected-(U2-PC14{slash}OSC32I-Pad3)") (class "Default")
      (node (ref "U2") (pin "3") (pinfunction "PC14/OSC32I_3") (pintype "passive"))
    )
    (net (code "104") (name "unconnected-(U2-PC15{slash}OSC32O-Pad4)") (class "Default")
      (node (ref "U2") (pin "4") (pinfunction "PC15/OSC32O_4") (pintype "passive"))
    )
  )
)
